# rgb-matrix-backpack-5.net
KiCad netlist of a schematic drawn in EAGLE
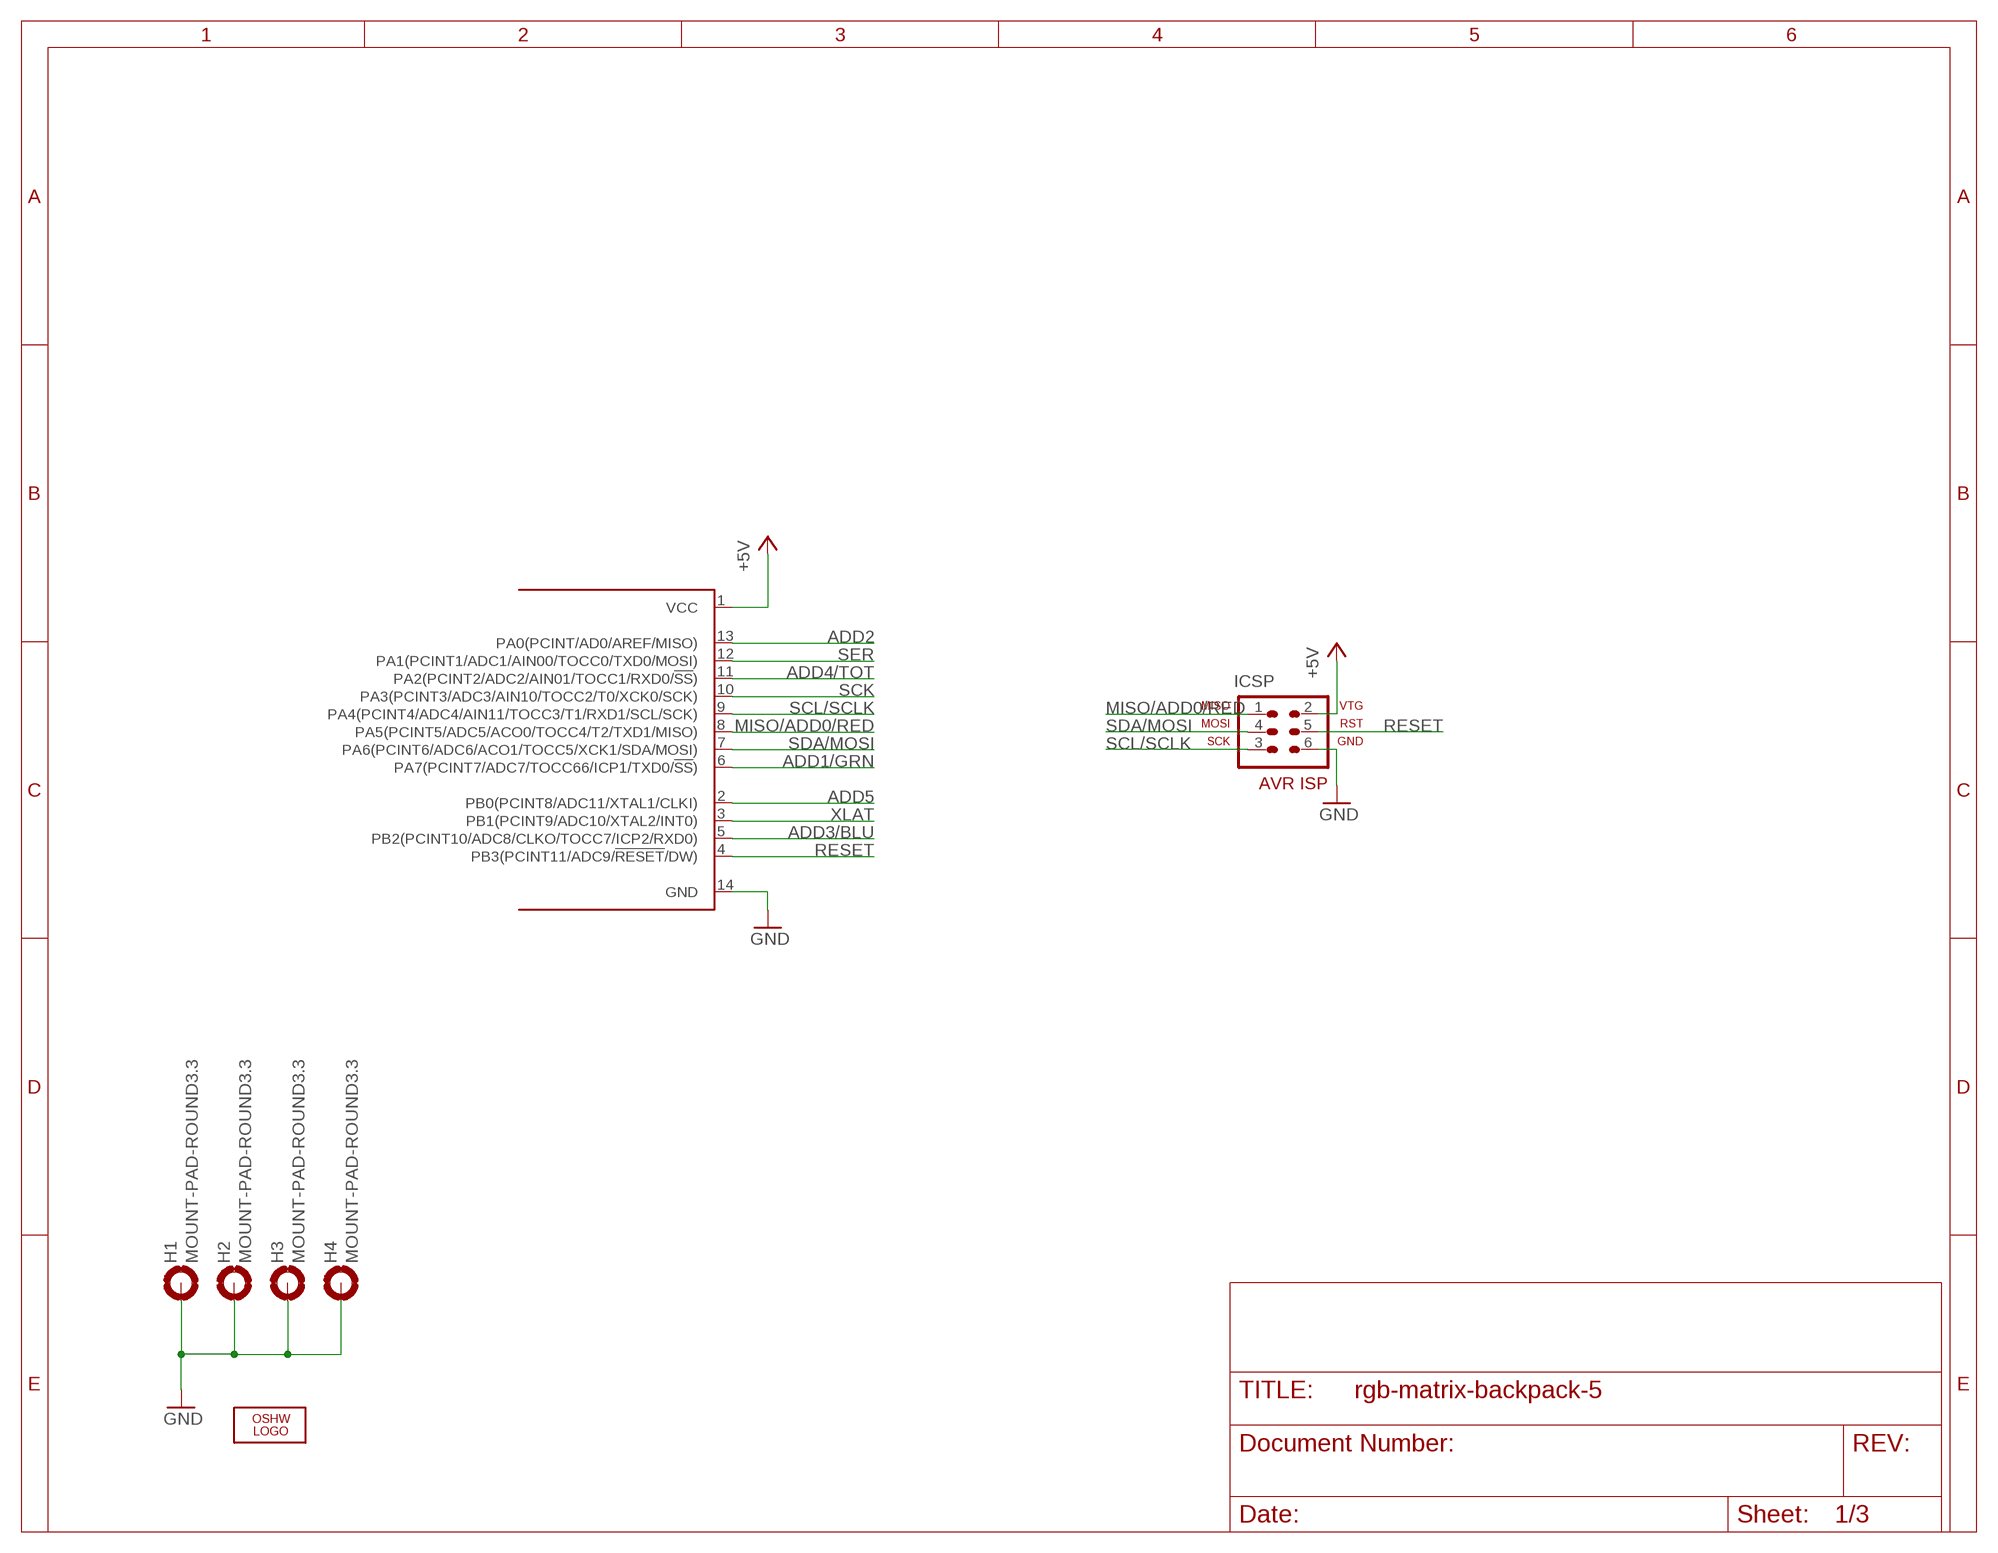
[diagram p0: schematic, sheet 1]
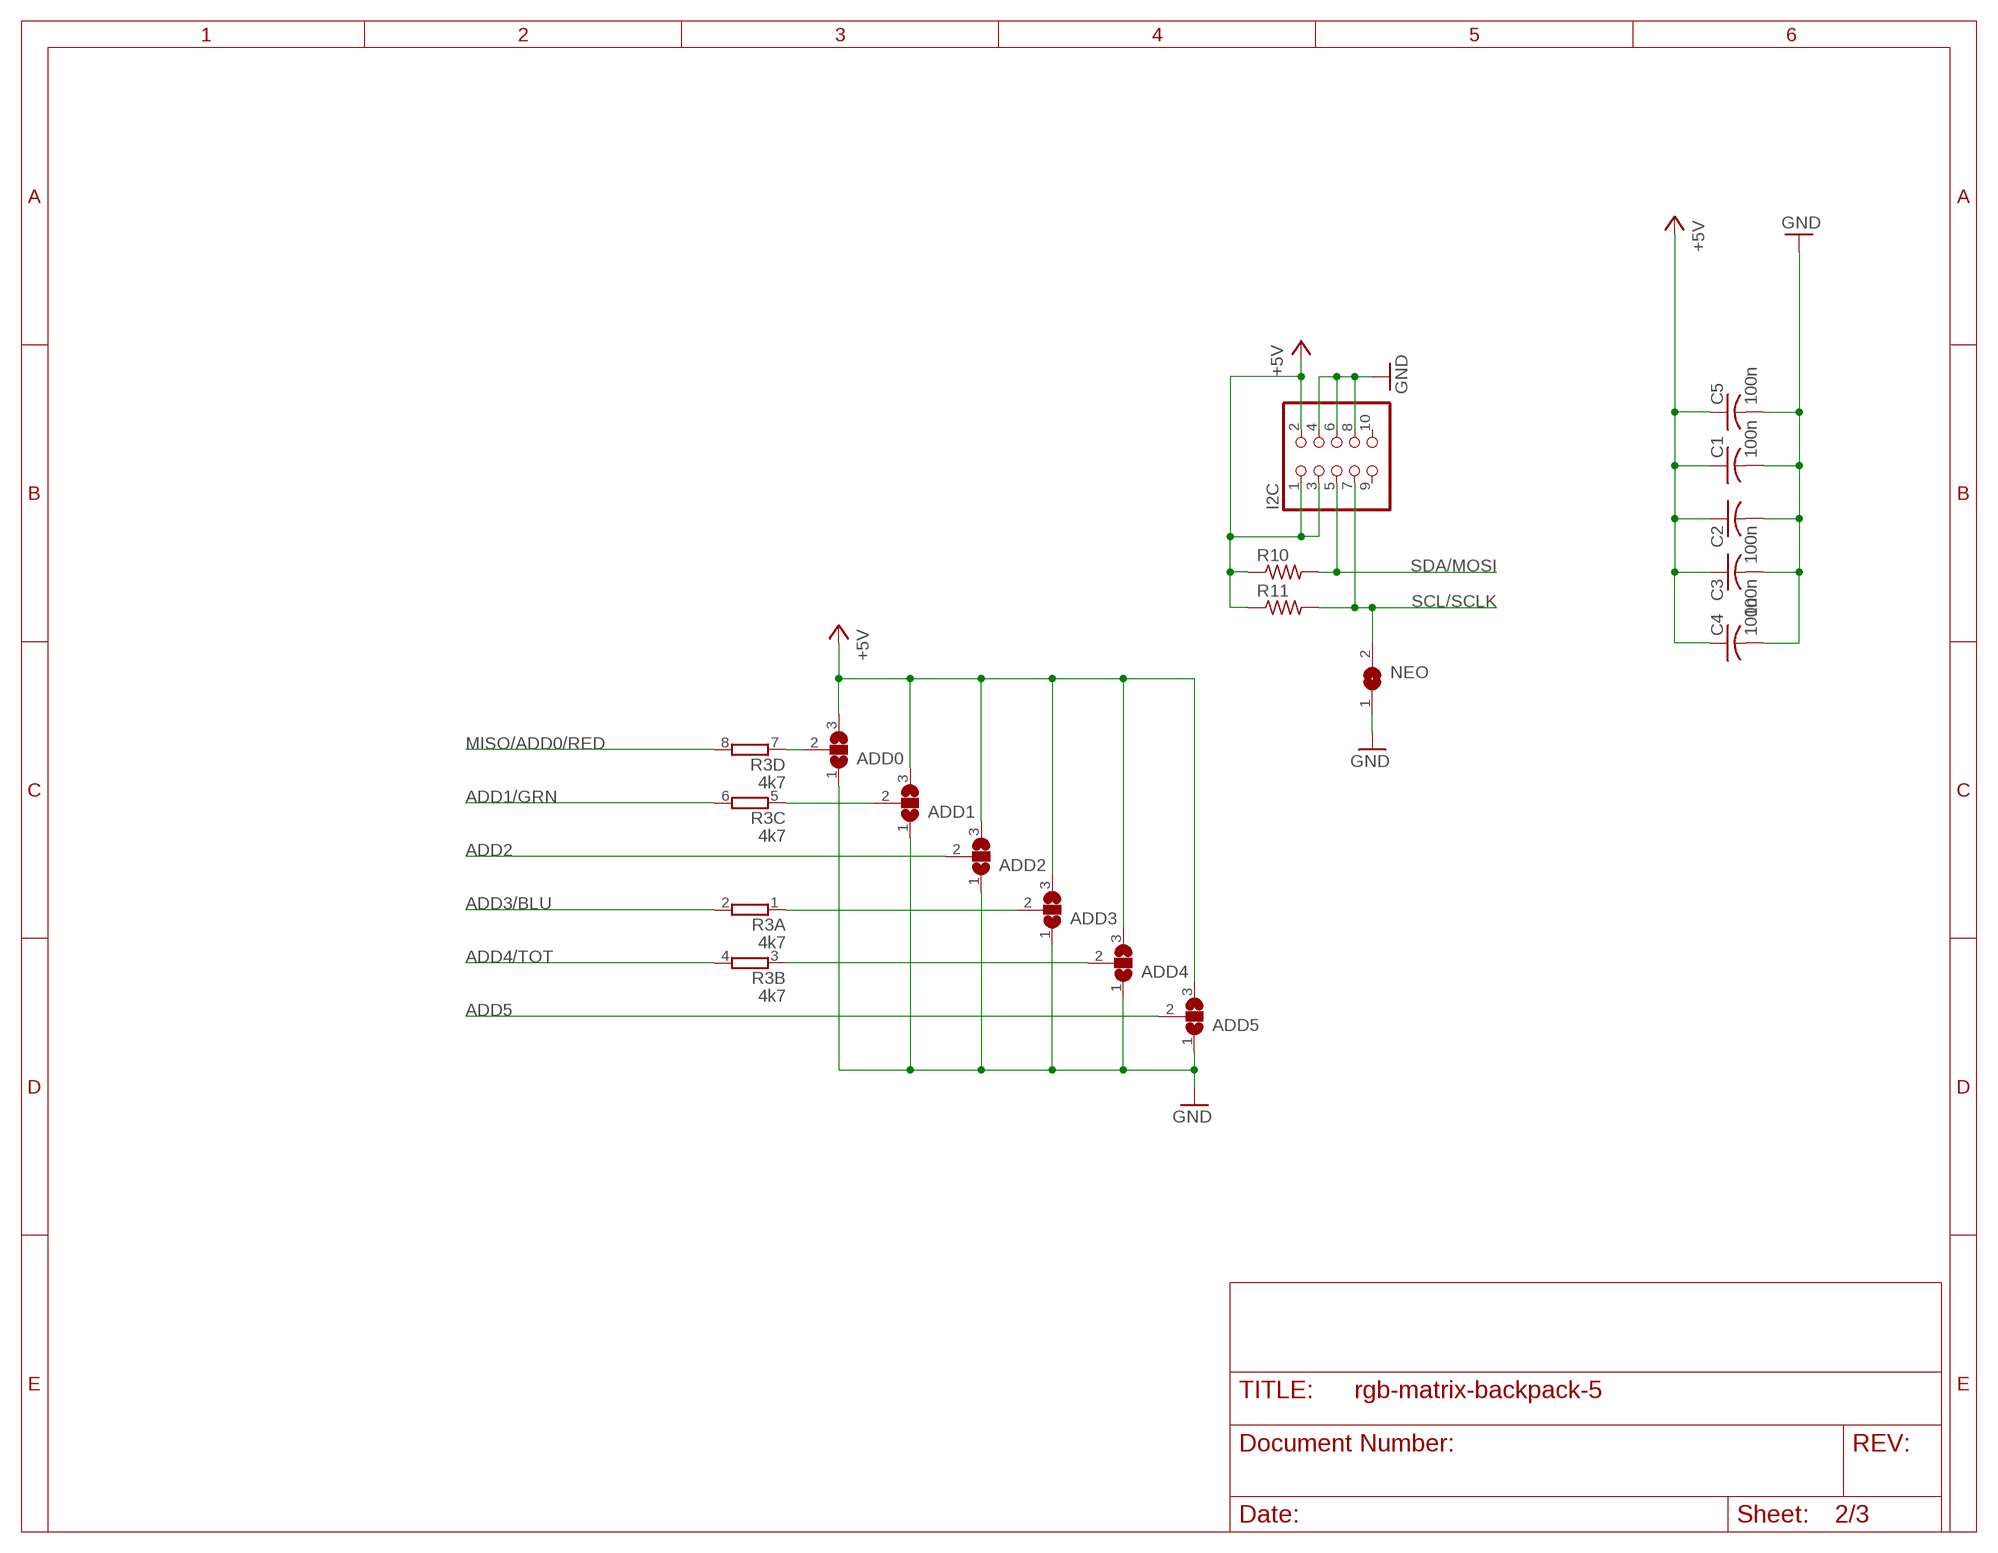
[diagram p1: schematic, sheet 2]
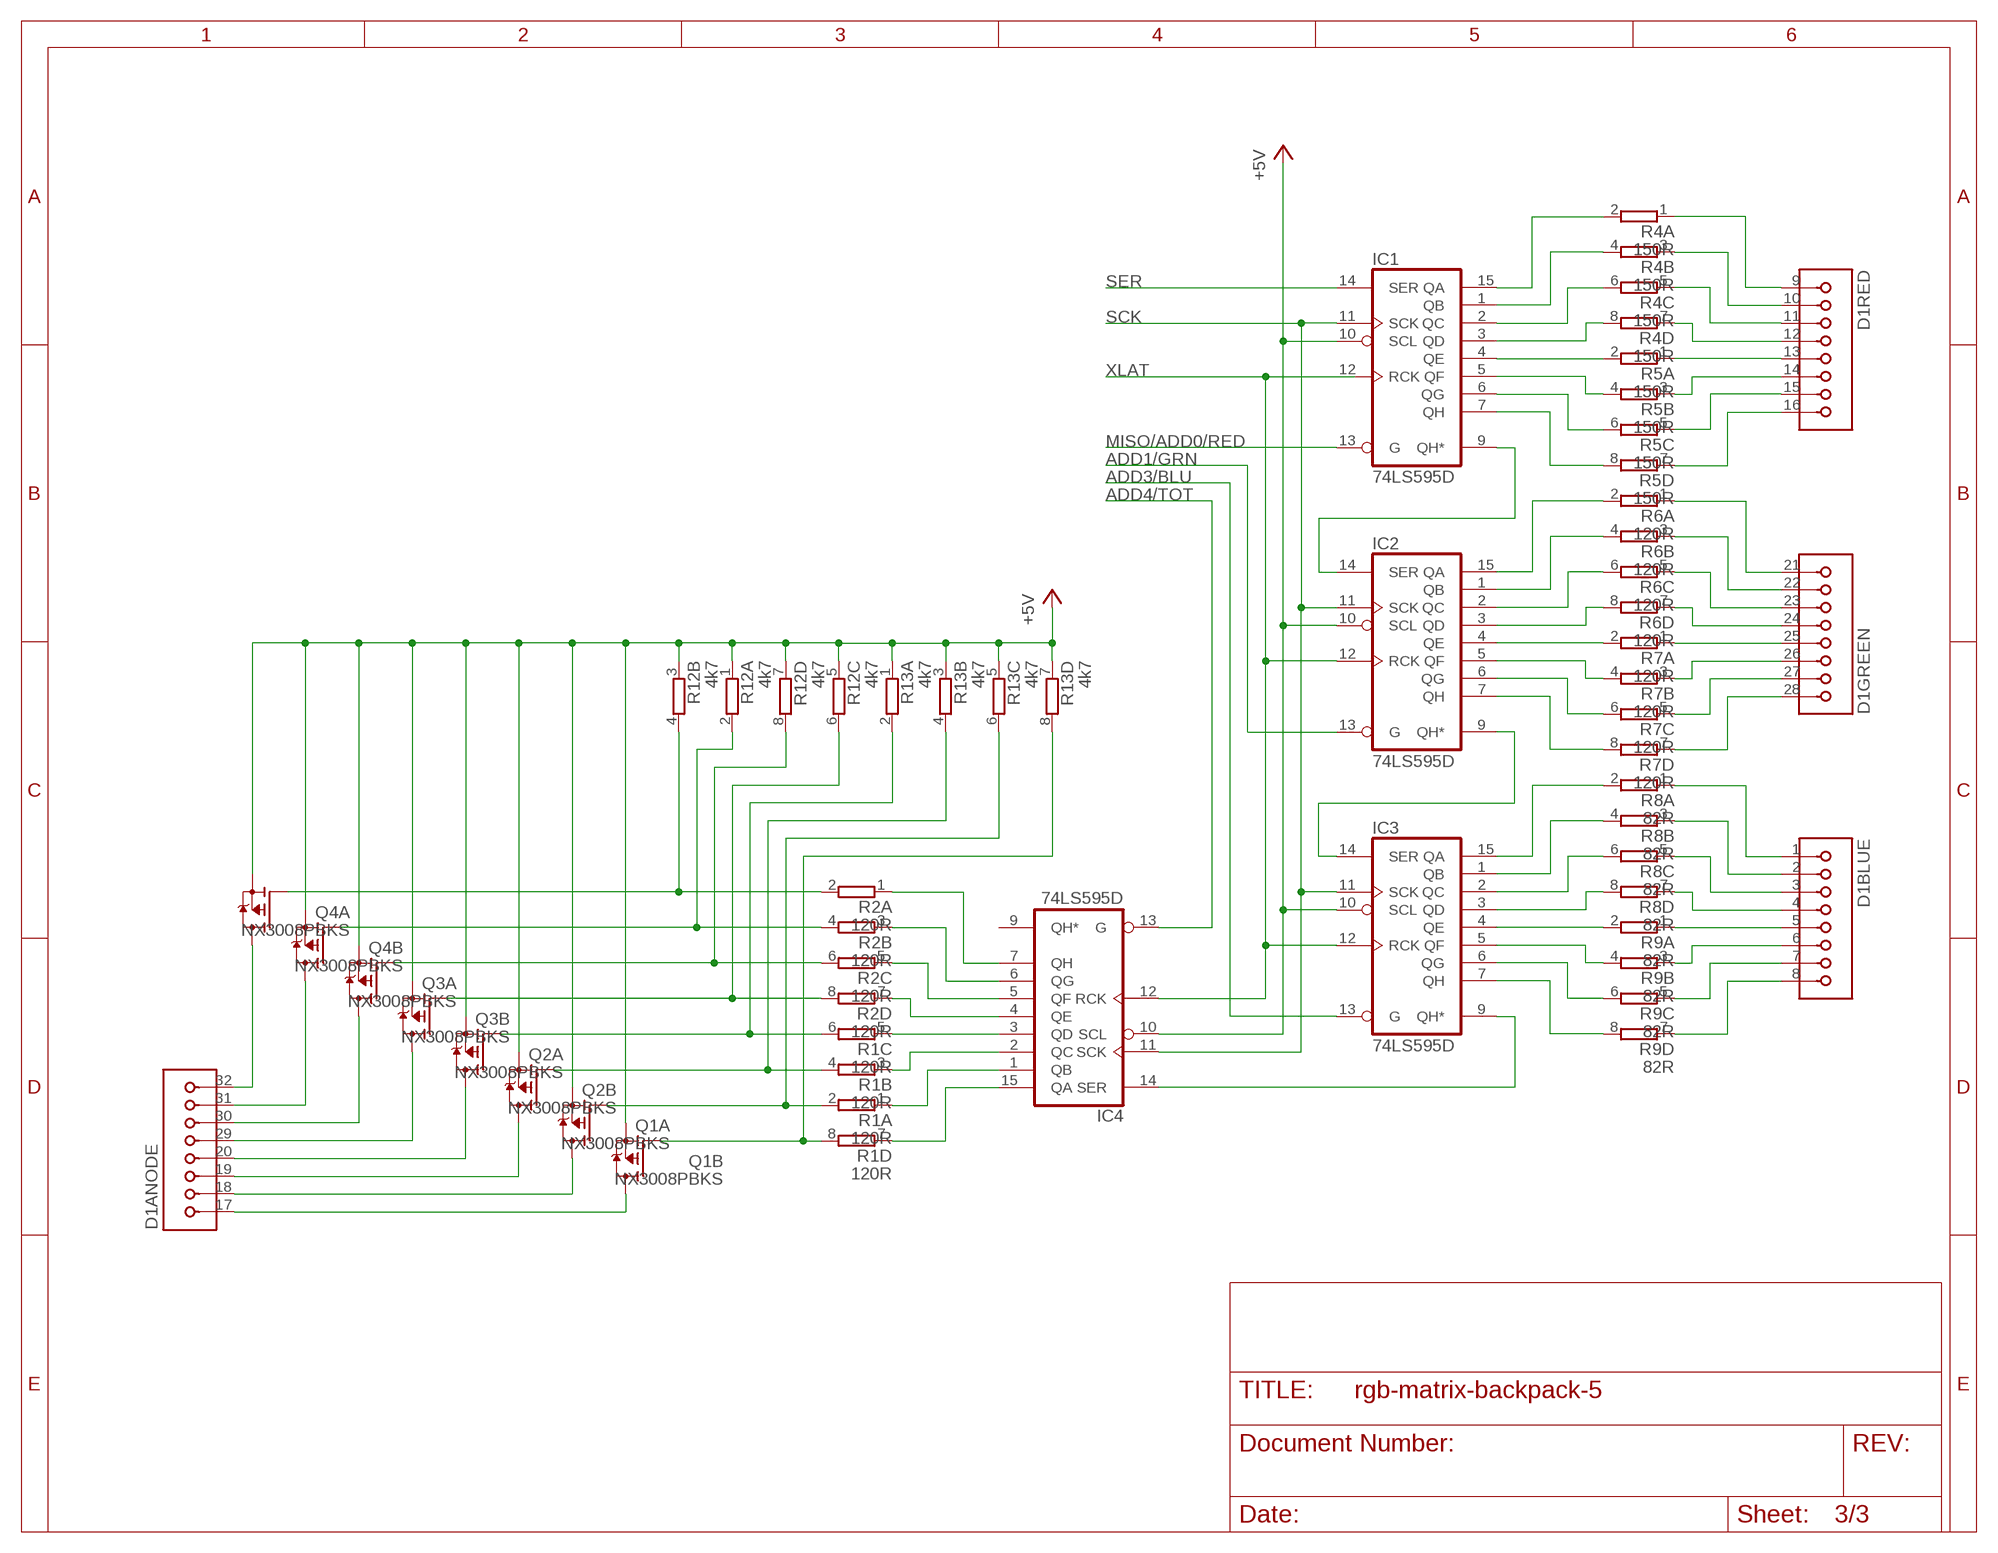
[diagram p2: schematic, sheet 3]

(export (version "E")
  (design (tool "Eeschema 10.0.6"))
  (components
    (comp (ref "D1")
      (value "60MM-8X8-RGB-LED-ARRAY")
      (footprint "eagle-import:60MM-8X8-RGB-MATRIX")
      (fields (field (name "BOM") "EXCLUDE") (field (name "DNP") "T"))
      (libsource (lib "eagle-import") (part "60MM-8X8-RGB-LED-ARRAY"))
    )
    (comp (ref "IC1")
      (value "74LS595D")
      (footprint "eagle-import:SO16")
      (libsource (lib "eagle-import") (part "74595DLS"))
    )
    (comp (ref "IC2")
      (value "74LS595D")
      (footprint "eagle-import:SO16")
      (libsource (lib "eagle-import") (part "74595DLS"))
    )
    (comp (ref "IC3")
      (value "74LS595D")
      (footprint "eagle-import:SO16")
      (libsource (lib "eagle-import") (part "74595DLS"))
    )
    (comp (ref "IC4")
      (value "74LS595D")
      (footprint "eagle-import:SO16")
      (libsource (lib "eagle-import") (part "74595DLS"))
    )
    (comp (ref "Q1")
      (value "NX3008PBKS")
      (footprint "eagle-import:SOT363_INFINEON")
      (fields (field (name "PARTNO") "NX3008PBKS"))
      (libsource (lib "eagle-import") (part "BSD223P"))
    )
    (comp (ref "Q2")
      (value "NX3008PBKS")
      (footprint "eagle-import:SOT363_INFINEON")
      (libsource (lib "eagle-import") (part "BSD223P"))
    )
    (comp (ref "Q3")
      (value "NX3008PBKS")
      (footprint "eagle-import:SOT363_INFINEON")
      (libsource (lib "eagle-import") (part "BSD223P"))
    )
    (comp (ref "Q4")
      (value "NX3008PBKS")
      (footprint "eagle-import:SOT363_INFINEON")
      (libsource (lib "eagle-import") (part "BSD223P"))
    )
    (comp (ref "R1")
      (value "120R")
      (footprint "eagle-import:CTS742C083-RES")
      (fields (field (name "PARTNO") "742C083102JPTR"))
      (libsource (lib "eagle-import") (part "4R-NCTS742C083"))
    )
    (comp (ref "R2")
      (value "120R")
      (footprint "eagle-import:CTS742C083-RES")
      (fields (field (name "PARTNO") "742C083102JPTR"))
      (libsource (lib "eagle-import") (part "4R-NCTS742C083"))
    )
    (comp (ref "R4")
      (value "150R")
      (footprint "eagle-import:CTS742C083-RES")
      (fields (field (name "PARTNO") "742C083102JPTR"))
      (libsource (lib "eagle-import") (part "4R-NCTS742C083"))
    )
    (comp (ref "R5")
      (value "150R")
      (footprint "eagle-import:CTS742C083-RES")
      (fields (field (name "PARTNO") "742C083102JPTR"))
      (libsource (lib "eagle-import") (part "4R-NCTS742C083"))
    )
    (comp (ref "R6")
      (value "120R")
      (footprint "eagle-import:CTS742C083-RES")
      (fields (field (name "PARTNO") "742C083102JPTR"))
      (libsource (lib "eagle-import") (part "4R-NCTS742C083"))
    )
    (comp (ref "R7")
      (value "120R")
      (footprint "eagle-import:CTS742C083-RES")
      (fields (field (name "PARTNO") "742C083102JPTR"))
      (libsource (lib "eagle-import") (part "4R-NCTS742C083"))
    )
    (comp (ref "R8")
      (value "82R")
      (footprint "eagle-import:CTS742C083-RES")
      (fields (field (name "PARTNO") "742C083102JPTR"))
      (libsource (lib "eagle-import") (part "4R-NCTS742C083"))
    )
    (comp (ref "R9")
      (value "82R")
      (footprint "eagle-import:CTS742C083-RES")
      (fields (field (name "PARTNO") "742C083102JPTR"))
      (libsource (lib "eagle-import") (part "4R-NCTS742C083"))
    )
    (comp (ref "R12")
      (value "4k7")
      (footprint "eagle-import:CTS742C083-RES")
      (fields (field (name "PARTNO") "742C083102JPTR"))
      (libsource (lib "eagle-import") (part "4R-NCTS742C083"))
    )
    (comp (ref "R13")
      (value "4k7")
      (footprint "eagle-import:CTS742C083-RES")
      (fields (field (name "PARTNO") "742C083102JPTR"))
      (libsource (lib "eagle-import") (part "4R-NCTS742C083"))
    )
    (comp (ref "H1")
      (value "MOUNT-PAD-ROUND3.3")
      (footprint "eagle-import:3,3-PAD")
      (libsource (lib "eagle-import") (part "MOUNT-PAD-ROUND3.3"))
    )
    (comp (ref "H2")
      (value "MOUNT-PAD-ROUND3.3")
      (footprint "eagle-import:3,3-PAD")
      (libsource (lib "eagle-import") (part "MOUNT-PAD-ROUND3.3"))
    )
    (comp (ref "H3")
      (value "MOUNT-PAD-ROUND3.3")
      (footprint "eagle-import:3,3-PAD")
      (libsource (lib "eagle-import") (part "MOUNT-PAD-ROUND3.3"))
    )
    (comp (ref "H4")
      (value "MOUNT-PAD-ROUND3.3")
      (footprint "eagle-import:3,3-PAD")
      (libsource (lib "eagle-import") (part "MOUNT-PAD-ROUND3.3"))
    )
    (comp (ref "ICSP")
      (value "AVR-ISP-6")
      (footprint "eagle-import:AVR-ISP-6")
      (libsource (lib "eagle-import") (part "AVR-ISP-6"))
    )
    (comp (ref "LOGO1")
      (value "OSHW_LOGO_FILLX0350-NT")
      (footprint "eagle-import:OSHW_FILLX350_NOTEXT")
      (libsource (lib "eagle-import") (part "OSHW_LOGO_FILLX0350-NT"))
    )
    (comp (ref "U1")
      (value "ATTINY841-SU")
      (footprint "eagle-import:SO14")
      (libsource (lib "eagle-import") (part "ATTINY841-SU"))
    )
    (comp (ref "ADD0")
      (value "SJ2W")
      (footprint "eagle-import:SJ_2")
      (libsource (lib "eagle-import") (part "SJ2W"))
    )
    (comp (ref "ADD1")
      (value "SJ2W")
      (footprint "eagle-import:SJ_2")
      (libsource (lib "eagle-import") (part "SJ2W"))
    )
    (comp (ref "ADD2")
      (value "SJ2W")
      (footprint "eagle-import:SJ_2")
      (libsource (lib "eagle-import") (part "SJ2W"))
    )
    (comp (ref "ADD3")
      (value "SJ2W")
      (footprint "eagle-import:SJ_2")
      (libsource (lib "eagle-import") (part "SJ2W"))
    )
    (comp (ref "ADD4")
      (value "SJ2W")
      (footprint "eagle-import:SJ_2")
      (libsource (lib "eagle-import") (part "SJ2W"))
    )
    (comp (ref "ADD5")
      (value "SJ2W")
      (footprint "eagle-import:SJ_2")
      (libsource (lib "eagle-import") (part "SJ2W"))
    )
    (comp (ref "C1")
      (value "100n")
      (footprint "eagle-import:C0603")
      (fields (field (name "PARTNO") "CC0603MRY5V9BB104"))
      (libsource (lib "eagle-import") (part "C-USC0603"))
    )
    (comp (ref "C2")
      (value "100n")
      (footprint "eagle-import:C0603")
      (fields (field (name "PARTNO") "CC0603MRY5V9BB104"))
      (libsource (lib "eagle-import") (part "C-USC0603"))
    )
    (comp (ref "C3")
      (value "100n")
      (footprint "eagle-import:C0603")
      (fields (field (name "PARTNO") "CC0603ZRY5V7BB105"))
      (libsource (lib "eagle-import") (part "C-USC0603"))
    )
    (comp (ref "C4")
      (value "100n")
      (footprint "eagle-import:C0603")
      (fields (field (name "PARTNO") "CC0603MRY5V9BB104"))
      (libsource (lib "eagle-import") (part "C-USC0603"))
    )
    (comp (ref "C5")
      (value "100n")
      (footprint "eagle-import:C0603")
      (fields (field (name "PARTNO") "CC0603MRY5V9BB104"))
      (libsource (lib "eagle-import") (part "C-USC0603"))
    )
    (comp (ref "I2C")
      (value "PINHD-2X5_2.54-90°")
      (footprint "eagle-import:2X05_90")
      (libsource (lib "eagle-import") (part "PINHD-2X5_2.54-90°"))
    )
    (comp (ref "NEO") (value "SJ") (footprint "eagle-import:SJ") (libsource (lib "eagle-import") (part "SJ")))
    (comp (ref "R3")
      (value "4k7")
      (footprint "eagle-import:CTS742C083-RES")
      (fields (field (name "PARTNO") "742C083102JPTR"))
      (libsource (lib "eagle-import") (part "4R-NCTS742C083"))
    )
    (comp (ref "R10")
      (value "R-US_0207/2V")
      (footprint "eagle-import:0207_2V")
      (fields (field (name "PARTNO") "CF14JT4K70"))
      (libsource (lib "eagle-import") (part "R-US_0207/2V"))
    )
    (comp (ref "R11")
      (value "R-US_0207/2V")
      (footprint "eagle-import:0207_2V")
      (fields (field (name "PARTNO") "CF14JT4K70"))
      (libsource (lib "eagle-import") (part "R-US_0207/2V"))
    )
  )
  (nets
    (net (code "1") (name "+5V") (class "Default")
      (node (ref "ADD0") (pin "3") (pinfunction "3_3") (pintype "passive"))
      (node (ref "ADD1") (pin "3") (pinfunction "3_3") (pintype "passive"))
      (node (ref "ADD2") (pin "3") (pinfunction "3_3") (pintype "passive"))
      (node (ref "ADD3") (pin "3") (pinfunction "3_3") (pintype "passive"))
      (node (ref "ADD4") (pin "3") (pinfunction "3_3") (pintype "passive"))
      (node (ref "ADD5") (pin "3") (pinfunction "3_3") (pintype "passive"))
      (node (ref "C1") (pin "1") (pinfunction "1_1") (pintype "passive"))
      (node (ref "C2") (pin "1") (pinfunction "1_1") (pintype "passive"))
      (node (ref "C3") (pin "1") (pinfunction "1_1") (pintype "passive"))
      (node (ref "C4") (pin "1") (pinfunction "1_1") (pintype "passive"))
      (node (ref "C5") (pin "1") (pinfunction "1_1") (pintype "passive"))
      (node (ref "I2C") (pin "1") (pinfunction "1_1") (pintype "passive"))
      (node (ref "I2C") (pin "2") (pinfunction "2_2") (pintype "passive"))
      (node (ref "I2C") (pin "3") (pinfunction "3_3") (pintype "passive"))
      (node (ref "IC1") (pin "10") (pinfunction "SCL_10") (pintype "input"))
      (node (ref "IC2") (pin "10") (pinfunction "SCL_10") (pintype "input"))
      (node (ref "IC3") (pin "10") (pinfunction "SCL_10") (pintype "input"))
      (node (ref "IC4") (pin "10") (pinfunction "SCL_10") (pintype "input"))
      (node (ref "ICSP") (pin "2") (pinfunction "2_2") (pintype "passive"))
      (node (ref "Q1") (pin "1") (pinfunction "S_1") (pintype "passive"))
      (node (ref "Q1") (pin "4") (pinfunction "S_4") (pintype "passive"))
      (node (ref "Q2") (pin "1") (pinfunction "S_1") (pintype "passive"))
      (node (ref "Q2") (pin "4") (pinfunction "S_4") (pintype "passive"))
      (node (ref "Q3") (pin "1") (pinfunction "S_1") (pintype "passive"))
      (node (ref "Q3") (pin "4") (pinfunction "S_4") (pintype "passive"))
      (node (ref "Q4") (pin "1") (pinfunction "S_1") (pintype "passive"))
      (node (ref "Q4") (pin "4") (pinfunction "S_4") (pintype "passive"))
      (node (ref "R10") (pin "1") (pinfunction "1_1") (pintype "passive"))
      (node (ref "R11") (pin "1") (pinfunction "1_1") (pintype "passive"))
      (node (ref "R12") (pin "1") (pinfunction "1_1") (pintype "passive"))
      (node (ref "R12") (pin "3") (pinfunction "1_3") (pintype "passive"))
      (node (ref "R12") (pin "5") (pinfunction "1_5") (pintype "passive"))
      (node (ref "R12") (pin "7") (pinfunction "1_7") (pintype "passive"))
      (node (ref "R13") (pin "1") (pinfunction "1_1") (pintype "passive"))
      (node (ref "R13") (pin "3") (pinfunction "1_3") (pintype "passive"))
      (node (ref "R13") (pin "5") (pinfunction "1_5") (pintype "passive"))
      (node (ref "R13") (pin "7") (pinfunction "1_7") (pintype "passive"))
      (node (ref "U1") (pin "1") (pinfunction "VCC_1") (pintype "bidirectional"))
    )
    (net (code "2") (name "ADD1{slash}GRN") (class "Default")
      (node (ref "IC2") (pin "13") (pinfunction "G_13") (pintype "input"))
      (node (ref "R3") (pin "6") (pinfunction "2_6") (pintype "passive"))
      (node (ref "U1") (pin "6") (pinfunction "PA7(PCINT7/ADC7/TOCC66/ICP1/TXD0/~{SS})_6") (pintype "bidirectional"))
    )
    (net (code "3") (name "ADD2") (class "Default")
      (node (ref "ADD2") (pin "2") (pinfunction "2_2") (pintype "passive"))
      (node (ref "U1") (pin "13") (pinfunction "PA0(PCINT/AD0/AREF/MISO)_13") (pintype "bidirectional"))
    )
    (net (code "4") (name "ADD3{slash}BLU") (class "Default")
      (node (ref "IC3") (pin "13") (pinfunction "G_13") (pintype "input"))
      (node (ref "R3") (pin "2") (pinfunction "2_2") (pintype "passive"))
      (node (ref "U1") (pin "5") (pinfunction "PB2(PCINT10/ADC8/CLKO/TOCC7/ICP2/RXD0)_5") (pintype "bidirectional"))
    )
    (net (code "5") (name "ADD4{slash}TOT") (class "Default")
      (node (ref "IC4") (pin "13") (pinfunction "G_13") (pintype "input"))
      (node (ref "R3") (pin "4") (pinfunction "2_4") (pintype "passive"))
      (node (ref "U1") (pin "11") (pinfunction "PA2(PCINT2/ADC2/AIN01/TOCC1/RXD0/~{SS})_11") (pintype "bidirectional"))
    )
    (net (code "6") (name "ADD5") (class "Default")
      (node (ref "ADD5") (pin "2") (pinfunction "2_2") (pintype "passive"))
      (node (ref "U1") (pin "2") (pinfunction "PB0(PCINT8/ADC11/XTAL1/CLKI)_2") (pintype "bidirectional"))
    )
    (net (code "7") (name "GND") (class "Default")
      (node (ref "ADD0") (pin "1") (pinfunction "1_1") (pintype "passive"))
      (node (ref "ADD1") (pin "1") (pinfunction "1_1") (pintype "passive"))
      (node (ref "ADD2") (pin "1") (pinfunction "1_1") (pintype "passive"))
      (node (ref "ADD3") (pin "1") (pinfunction "1_1") (pintype "passive"))
      (node (ref "ADD4") (pin "1") (pinfunction "1_1") (pintype "passive"))
      (node (ref "ADD5") (pin "1") (pinfunction "1_1") (pintype "passive"))
      (node (ref "C1") (pin "2") (pinfunction "2_2") (pintype "passive"))
      (node (ref "C2") (pin "2") (pinfunction "2_2") (pintype "passive"))
      (node (ref "C3") (pin "2") (pinfunction "2_2") (pintype "passive"))
      (node (ref "C4") (pin "2") (pinfunction "2_2") (pintype "passive"))
      (node (ref "C5") (pin "2") (pinfunction "2_2") (pintype "passive"))
      (node (ref "H1") (pin "B3,3") (pinfunction "MOUNT_B3,3") (pintype "passive"))
      (node (ref "H2") (pin "B3,3") (pinfunction "MOUNT_B3,3") (pintype "passive"))
      (node (ref "H3") (pin "B3,3") (pinfunction "MOUNT_B3,3") (pintype "passive"))
      (node (ref "H4") (pin "B3,3") (pinfunction "MOUNT_B3,3") (pintype "passive"))
      (node (ref "I2C") (pin "4") (pinfunction "4_4") (pintype "passive"))
      (node (ref "I2C") (pin "6") (pinfunction "6_6") (pintype "passive"))
      (node (ref "I2C") (pin "8") (pinfunction "8_8") (pintype "passive"))
      (node (ref "ICSP") (pin "6") (pinfunction "6_6") (pintype "passive"))
      (node (ref "NEO") (pin "1") (pinfunction "1_1") (pintype "passive"))
      (node (ref "U1") (pin "14") (pinfunction "GND_14") (pintype "bidirectional"))
    )
    (net (code "8") (name "MISO{slash}ADD0{slash}RED") (class "Default")
      (node (ref "IC1") (pin "13") (pinfunction "G_13") (pintype "input"))
      (node (ref "ICSP") (pin "1") (pinfunction "1_1") (pintype "passive"))
      (node (ref "R3") (pin "8") (pinfunction "2_8") (pintype "passive"))
      (node (ref "U1") (pin "8") (pinfunction "PA5(PCINT5/ADC5/ACO0/TOCC4/T2/TXD1/MISO)_8") (pintype "bidirectional"))
    )
    (net (code "9") (name "Net-(ADD3-Pad2)") (class "Default")
      (node (ref "ADD3") (pin "2") (pinfunction "2_2") (pintype "passive"))
      (node (ref "R3") (pin "1") (pinfunction "1_1") (pintype "passive"))
    )
    (net (code "10") (name "Net-(D1-Pad1)") (class "Default")
      (node (ref "D1") (pin "1") (pinfunction "1_1") (pintype "bidirectional"))
      (node (ref "R8") (pin "1") (pinfunction "1_1") (pintype "passive"))
    )
    (net (code "11") (name "Net-(D1-Pad5)") (class "Default")
      (node (ref "D1") (pin "5") (pinfunction "5_5") (pintype "bidirectional"))
      (node (ref "R9") (pin "1") (pinfunction "1_1") (pintype "passive"))
    )
    (net (code "12") (name "Net-(D1A-1)") (class "Default")
      (node (ref "D1") (pin "17") (pinfunction "1_17") (pintype "bidirectional"))
      (node (ref "Q1") (pin "3") (pinfunction "D_3") (pintype "passive"))
    )
    (net (code "13") (name "Net-(D1A-2)") (class "Default")
      (node (ref "D1") (pin "18") (pinfunction "2_18") (pintype "bidirectional"))
      (node (ref "Q1") (pin "6") (pinfunction "D_6") (pintype "passive"))
    )
    (net (code "14") (name "Net-(D1A-3)") (class "Default")
      (node (ref "D1") (pin "19") (pinfunction "3_19") (pintype "bidirectional"))
      (node (ref "Q2") (pin "3") (pinfunction "D_3") (pintype "passive"))
    )
    (net (code "15") (name "Net-(D1A-4)") (class "Default")
      (node (ref "D1") (pin "20") (pinfunction "4_20") (pintype "bidirectional"))
      (node (ref "Q2") (pin "6") (pinfunction "D_6") (pintype "passive"))
    )
    (net (code "16") (name "Net-(D1A-5)") (class "Default")
      (node (ref "D1") (pin "29") (pinfunction "5_29") (pintype "bidirectional"))
      (node (ref "Q3") (pin "3") (pinfunction "D_3") (pintype "passive"))
    )
    (net (code "17") (name "Net-(D1A-6)") (class "Default")
      (node (ref "D1") (pin "30") (pinfunction "6_30") (pintype "bidirectional"))
      (node (ref "Q3") (pin "6") (pinfunction "D_6") (pintype "passive"))
    )
    (net (code "18") (name "Net-(D1A-7)") (class "Default")
      (node (ref "D1") (pin "31") (pinfunction "7_31") (pintype "bidirectional"))
      (node (ref "Q4") (pin "3") (pinfunction "D_3") (pintype "passive"))
    )
    (net (code "19") (name "Net-(D1A-8)") (class "Default")
      (node (ref "D1") (pin "32") (pinfunction "8_32") (pintype "bidirectional"))
      (node (ref "Q4") (pin "6") (pinfunction "D_6") (pintype "passive"))
    )
    (net (code "20") (name "Net-(D1C-1)") (class "Default")
      (node (ref "D1") (pin "28") (pinfunction "1_28") (pintype "bidirectional"))
      (node (ref "R7") (pin "7") (pinfunction "1_7") (pintype "passive"))
    )
    (net (code "21") (name "Net-(D1C-2)") (class "Default")
      (node (ref "D1") (pin "27") (pinfunction "2_27") (pintype "bidirectional"))
      (node (ref "R7") (pin "5") (pinfunction "1_5") (pintype "passive"))
    )
    (net (code "22") (name "Net-(D1C-3)") (class "Default")
      (node (ref "D1") (pin "26") (pinfunction "3_26") (pintype "bidirectional"))
      (node (ref "R7") (pin "3") (pinfunction "1_3") (pintype "passive"))
    )
    (net (code "23") (name "Net-(D1C-4)") (class "Default")
      (node (ref "D1") (pin "25") (pinfunction "4_25") (pintype "bidirectional"))
      (node (ref "R7") (pin "1") (pinfunction "1_1") (pintype "passive"))
    )
    (net (code "24") (name "Net-(D1C-5)") (class "Default")
      (node (ref "D1") (pin "24") (pinfunction "5_24") (pintype "bidirectional"))
      (node (ref "R6") (pin "7") (pinfunction "1_7") (pintype "passive"))
    )
    (net (code "25") (name "Net-(D1C-6)") (class "Default")
      (node (ref "D1") (pin "23") (pinfunction "6_23") (pintype "bidirectional"))
      (node (ref "R6") (pin "5") (pinfunction "1_5") (pintype "passive"))
    )
    (net (code "26") (name "Net-(D1C-7)") (class "Default")
      (node (ref "D1") (pin "22") (pinfunction "7_22") (pintype "bidirectional"))
      (node (ref "R6") (pin "3") (pinfunction "1_3") (pintype "passive"))
    )
    (net (code "27") (name "Net-(D1C-8)") (class "Default")
      (node (ref "D1") (pin "21") (pinfunction "8_21") (pintype "bidirectional"))
      (node (ref "R6") (pin "1") (pinfunction "1_1") (pintype "passive"))
    )
    (net (code "28") (name "Net-(D1D-1)") (class "Default")
      (node (ref "D1") (pin "9") (pinfunction "1_9") (pintype "bidirectional"))
      (node (ref "R4") (pin "1") (pinfunction "1_1") (pintype "passive"))
    )
    (net (code "29") (name "Net-(D1D-2)") (class "Default")
      (node (ref "D1") (pin "10") (pinfunction "2_10") (pintype "bidirectional"))
      (node (ref "R4") (pin "3") (pinfunction "1_3") (pintype "passive"))
    )
    (net (code "30") (name "Net-(D1D-3)") (class "Default")
      (node (ref "D1") (pin "11") (pinfunction "3_11") (pintype "bidirectional"))
      (node (ref "R4") (pin "5") (pinfunction "1_5") (pintype "passive"))
    )
    (net (code "31") (name "Net-(D1D-4)") (class "Default")
      (node (ref "D1") (pin "12") (pinfunction "4_12") (pintype "bidirectional"))
      (node (ref "R4") (pin "7") (pinfunction "1_7") (pintype "passive"))
    )
    (net (code "32") (name "Net-(D1D-5)") (class "Default")
      (node (ref "D1") (pin "13") (pinfunction "5_13") (pintype "bidirectional"))
      (node (ref "R5") (pin "1") (pinfunction "1_1") (pintype "passive"))
    )
    (net (code "33") (name "Net-(D1D-6)") (class "Default")
      (node (ref "D1") (pin "14") (pinfunction "6_14") (pintype "bidirectional"))
      (node (ref "R5") (pin "3") (pinfunction "1_3") (pintype "passive"))
    )
    (net (code "34") (name "Net-(D1D-7)") (class "Default")
      (node (ref "D1") (pin "15") (pinfunction "7_15") (pintype "bidirectional"))
      (node (ref "R5") (pin "5") (pinfunction "1_5") (pintype "passive"))
    )
    (net (code "35") (name "Net-(D1D-8)") (class "Default")
      (node (ref "D1") (pin "16") (pinfunction "8_16") (pintype "bidirectional"))
      (node (ref "R5") (pin "7") (pinfunction "1_7") (pintype "passive"))
    )
    (net (code "36") (name "Net-(IC1A-QA)") (class "Default")
      (node (ref "IC1") (pin "15") (pinfunction "QA_15") (pintype "tri_state"))
      (node (ref "R4") (pin "2") (pinfunction "2_2") (pintype "passive"))
    )
    (net (code "37") (name "Net-(IC1A-QB)") (class "Default")
      (node (ref "IC1") (pin "1") (pinfunction "QB_1") (pintype "tri_state"))
      (node (ref "R4") (pin "4") (pinfunction "2_4") (pintype "passive"))
    )
    (net (code "38") (name "Net-(IC1A-QC)") (class "Default")
      (node (ref "IC1") (pin "2") (pinfunction "QC_2") (pintype "tri_state"))
      (node (ref "R4") (pin "6") (pinfunction "2_6") (pintype "passive"))
    )
    (net (code "39") (name "Net-(IC1A-QD)") (class "Default")
      (node (ref "IC1") (pin "3") (pinfunction "QD_3") (pintype "tri_state"))
      (node (ref "R4") (pin "8") (pinfunction "2_8") (pintype "passive"))
    )
    (net (code "40") (name "Net-(IC1A-QE)") (class "Default")
      (node (ref "IC1") (pin "4") (pinfunction "QE_4") (pintype "tri_state"))
      (node (ref "R5") (pin "2") (pinfunction "2_2") (pintype "passive"))
    )
    (net (code "41") (name "Net-(IC1A-QF)") (class "Default")
      (node (ref "IC1") (pin "5") (pinfunction "QF_5") (pintype "tri_state"))
      (node (ref "R5") (pin "4") (pinfunction "2_4") (pintype "passive"))
    )
    (net (code "42") (name "Net-(IC1A-QG)") (class "Default")
      (node (ref "IC1") (pin "6") (pinfunction "QG_6") (pintype "tri_state"))
      (node (ref "R5") (pin "6") (pinfunction "2_6") (pintype "passive"))
    )
    (net (code "43") (name "Net-(IC1A-QH)") (class "Default")
      (node (ref "IC1") (pin "7") (pinfunction "QH_7") (pintype "tri_state"))
      (node (ref "R5") (pin "8") (pinfunction "2_8") (pintype "passive"))
    )
    (net (code "44") (name "Net-(IC1A-QH*)") (class "Default")
      (node (ref "IC1") (pin "9") (pinfunction "QH*_9") (pintype "tri_state"))
      (node (ref "IC2") (pin "14") (pinfunction "SER_14") (pintype "input"))
    )
    (net (code "45") (name "Net-(IC2A-QA)") (class "Default")
      (node (ref "IC2") (pin "15") (pinfunction "QA_15") (pintype "tri_state"))
      (node (ref "R6") (pin "2") (pinfunction "2_2") (pintype "passive"))
    )
    (net (code "46") (name "Net-(IC2A-QB)") (class "Default")
      (node (ref "IC2") (pin "1") (pinfunction "QB_1") (pintype "tri_state"))
      (node (ref "R6") (pin "4") (pinfunction "2_4") (pintype "passive"))
    )
    (net (code "47") (name "Net-(IC2A-QC)") (class "Default")
      (node (ref "IC2") (pin "2") (pinfunction "QC_2") (pintype "tri_state"))
      (node (ref "R6") (pin "6") (pinfunction "2_6") (pintype "passive"))
    )
    (net (code "48") (name "Net-(IC2A-QD)") (class "Default")
      (node (ref "IC2") (pin "3") (pinfunction "QD_3") (pintype "tri_state"))
      (node (ref "R6") (pin "8") (pinfunction "2_8") (pintype "passive"))
    )
    (net (code "49") (name "Net-(IC2A-QE)") (class "Default")
      (node (ref "IC2") (pin "4") (pinfunction "QE_4") (pintype "tri_state"))
      (node (ref "R7") (pin "2") (pinfunction "2_2") (pintype "passive"))
    )
    (net (code "50") (name "Net-(IC2A-QF)") (class "Default")
      (node (ref "IC2") (pin "5") (pinfunction "QF_5") (pintype "tri_state"))
      (node (ref "R7") (pin "4") (pinfunction "2_4") (pintype "passive"))
    )
    (net (code "51") (name "Net-(IC2A-QG)") (class "Default")
      (node (ref "IC2") (pin "6") (pinfunction "QG_6") (pintype "tri_state"))
      (node (ref "R7") (pin "6") (pinfunction "2_6") (pintype "passive"))
    )
    (net (code "52") (name "Net-(IC2A-QH)") (class "Default")
      (node (ref "IC2") (pin "7") (pinfunction "QH_7") (pintype "tri_state"))
      (node (ref "R7") (pin "8") (pinfunction "2_8") (pintype "passive"))
    )
    (net (code "53") (name "Net-(IC2A-QH*)") (class "Default")
      (node (ref "IC2") (pin "9") (pinfunction "QH*_9") (pintype "tri_state"))
      (node (ref "IC3") (pin "14") (pinfunction "SER_14") (pintype "input"))
    )
    (net (code "54") (name "Net-(IC3A-QA)") (class "Default")
      (node (ref "IC3") (pin "15") (pinfunction "QA_15") (pintype "tri_state"))
      (node (ref "R8") (pin "2") (pinfunction "2_2") (pintype "passive"))
    )
    (net (code "55") (name "Net-(IC3A-QB)") (class "Default")
      (node (ref "IC3") (pin "1") (pinfunction "QB_1") (pintype "tri_state"))
      (node (ref "R8") (pin "4") (pinfunction "2_4") (pintype "passive"))
    )
    (net (code "56") (name "Net-(IC3A-QC)") (class "Default")
      (node (ref "IC3") (pin "2") (pinfunction "QC_2") (pintype "tri_state"))
      (node (ref "R8") (pin "6") (pinfunction "2_6") (pintype "passive"))
    )
    (net (code "57") (name "Net-(IC3A-QD)") (class "Default")
      (node (ref "IC3") (pin "3") (pinfunction "QD_3") (pintype "tri_state"))
      (node (ref "R8") (pin "8") (pinfunction "2_8") (pintype "passive"))
    )
    (net (code "58") (name "Net-(IC3A-QE)") (class "Default")
      (node (ref "IC3") (pin "4") (pinfunction "QE_4") (pintype "tri_state"))
      (node (ref "R9") (pin "2") (pinfunction "2_2") (pintype "passive"))
    )
    (net (code "59") (name "Net-(IC3A-QF)") (class "Default")
      (node (ref "IC3") (pin "5") (pinfunction "QF_5") (pintype "tri_state"))
      (node (ref "R9") (pin "4") (pinfunction "2_4") (pintype "passive"))
    )
    (net (code "60") (name "Net-(IC3A-QG)") (class "Default")
      (node (ref "IC3") (pin "6") (pinfunction "QG_6") (pintype "tri_state"))
      (node (ref "R9") (pin "6") (pinfunction "2_6") (pintype "passive"))
    )
    (net (code "61") (name "Net-(IC3A-QH)") (class "Default")
      (node (ref "IC3") (pin "7") (pinfunction "QH_7") (pintype "tri_state"))
      (node (ref "R9") (pin "8") (pinfunction "2_8") (pintype "passive"))
    )
    (net (code "62") (name "Net-(IC3A-QH*)") (class "Default")
      (node (ref "IC3") (pin "9") (pinfunction "QH*_9") (pintype "tri_state"))
      (node (ref "IC4") (pin "14") (pinfunction "SER_14") (pintype "input"))
    )
    (net (code "63") (name "Net-(IC4A-QA)") (class "Default")
      (node (ref "IC4") (pin "15") (pinfunction "QA_15") (pintype "tri_state"))
      (node (ref "R1") (pin "7") (pinfunction "1_7") (pintype "passive"))
    )
    (net (code "64") (name "Net-(IC4A-QB)") (class "Default")
      (node (ref "IC4") (pin "1") (pinfunction "QB_1") (pintype "tri_state"))
      (node (ref "R1") (pin "1") (pinfunction "1_1") (pintype "passive"))
    )
    (net (code "65") (name "Net-(IC4A-QC)") (class "Default")
      (node (ref "IC4") (pin "2") (pinfunction "QC_2") (pintype "tri_state"))
      (node (ref "R1") (pin "3") (pinfunction "1_3") (pintype "passive"))
    )
    (net (code "66") (name "Net-(IC4A-QD)") (class "Default")
      (node (ref "IC4") (pin "3") (pinfunction "QD_3") (pintype "tri_state"))
      (node (ref "R1") (pin "5") (pinfunction "1_5") (pintype "passive"))
    )
    (net (code "67") (name "Net-(IC4A-QE)") (class "Default")
      (node (ref "IC4") (pin "4") (pinfunction "QE_4") (pintype "tri_state"))
      (node (ref "R2") (pin "7") (pinfunction "1_7") (pintype "passive"))
    )
    (net (code "68") (name "Net-(IC4A-QF)") (class "Default")
      (node (ref "IC4") (pin "5") (pinfunction "QF_5") (pintype "tri_state"))
      (node (ref "R2") (pin "5") (pinfunction "1_5") (pintype "passive"))
    )
    (net (code "69") (name "Net-(IC4A-QG)") (class "Default")
      (node (ref "IC4") (pin "6") (pinfunction "QG_6") (pintype "tri_state"))
      (node (ref "R2") (pin "3") (pinfunction "1_3") (pintype "passive"))
    )
    (net (code "70") (name "Net-(IC4A-QH)") (class "Default")
      (node (ref "IC4") (pin "7") (pinfunction "QH_7") (pintype "tri_state"))
      (node (ref "R2") (pin "1") (pinfunction "1_1") (pintype "passive"))
    )
    (net (code "71") (name "Net-(Q1A-G)") (class "Default")
      (node (ref "Q1") (pin "2") (pinfunction "G_2") (pintype "passive"))
      (node (ref "R1") (pin "2") (pinfunction "2_2") (pintype "passive"))
      (node (ref "R13") (pin "6") (pinfunction "2_6") (pintype "passive"))
    )
    (net (code "72") (name "Net-(Q1B-G)") (class "Default")
      (node (ref "Q1") (pin "5") (pinfunction "G_5") (pintype "passive"))
      (node (ref "R1") (pin "8") (pinfunction "2_8") (pintype "passive"))
      (node (ref "R13") (pin "8") (pinfunction "2_8") (pintype "passive"))
    )
    (net (code "73") (name "Net-(Q2A-G)") (class "Default")
      (node (ref "Q2") (pin "2") (pinfunction "G_2") (pintype "passive"))
      (node (ref "R1") (pin "6") (pinfunction "2_6") (pintype "passive"))
      (node (ref "R13") (pin "2") (pinfunction "2_2") (pintype "passive"))
    )
    (net (code "74") (name "Net-(Q2B-G)") (class "Default")
      (node (ref "Q2") (pin "5") (pinfunction "G_5") (pintype "passive"))
      (node (ref "R1") (pin "4") (pinfunction "2_4") (pintype "passive"))
      (node (ref "R13") (pin "4") (pinfunction "2_4") (pintype "passive"))
    )
    (net (code "75") (name "Net-(Q3A-G)") (class "Default")
      (node (ref "Q3") (pin "2") (pinfunction "G_2") (pintype "passive"))
      (node (ref "R12") (pin "8") (pinfunction "2_8") (pintype "passive"))
      (node (ref "R2") (pin "6") (pinfunction "2_6") (pintype "passive"))
    )
    (net (code "76") (name "Net-(Q3B-G)") (class "Default")
      (node (ref "Q3") (pin "5") (pinfunction "G_5") (pintype "passive"))
      (node (ref "R12") (pin "6") (pinfunction "2_6") (pintype "passive"))
      (node (ref "R2") (pin "8") (pinfunction "2_8") (pintype "passive"))
    )
    (net (code "77") (name "Net-(Q4A-G)") (class "Default")
      (node (ref "Q4") (pin "2") (pinfunction "G_2") (pintype "passive"))
      (node (ref "R12") (pin "4") (pinfunction "2_4") (pintype "passive"))
      (node (ref "R2") (pin "2") (pinfunction "2_2") (pintype "passive"))
    )
    (net (code "78") (name "Net-(Q4B-G)") (class "Default")
      (node (ref "Q4") (pin "5") (pinfunction "G_5") (pintype "passive"))
      (node (ref "R12") (pin "2") (pinfunction "2_2") (pintype "passive"))
      (node (ref "R2") (pin "4") (pinfunction "2_4") (pintype "passive"))
    )
    (net (code "79") (name "Net-(R3B-1)") (class "Default")
      (node (ref "ADD4") (pin "2") (pinfunction "2_2") (pintype "passive"))
      (node (ref "R3") (pin "3") (pinfunction "1_3") (pintype "passive"))
    )
    (net (code "80") (name "Net-(R3C-1)") (class "Default")
      (node (ref "ADD1") (pin "2") (pinfunction "2_2") (pintype "passive"))
      (node (ref "R3") (pin "5") (pinfunction "1_5") (pintype "passive"))
    )
    (net (code "81") (name "Net-(R3D-1)") (class "Default")
      (node (ref "ADD0") (pin "2") (pinfunction "2_2") (pintype "passive"))
      (node (ref "R3") (pin "7") (pinfunction "1_7") (pintype "passive"))
    )
    (net (code "82") (name "Net-(R8B-1)") (class "Default")
      (node (ref "D1") (pin "2") (pinfunction "2_2") (pintype "bidirectional"))
      (node (ref "R8") (pin "3") (pinfunction "1_3") (pintype "passive"))
    )
    (net (code "83") (name "Net-(R8C-1)") (class "Default")
      (node (ref "D1") (pin "3") (pinfunction "3_3") (pintype "bidirectional"))
      (node (ref "R8") (pin "5") (pinfunction "1_5") (pintype "passive"))
    )
    (net (code "84") (name "Net-(R8D-1)") (class "Default")
      (node (ref "D1") (pin "4") (pinfunction "4_4") (pintype "bidirectional"))
      (node (ref "R8") (pin "7") (pinfunction "1_7") (pintype "passive"))
    )
    (net (code "85") (name "Net-(R9B-1)") (class "Default")
      (node (ref "D1") (pin "6") (pinfunction "6_6") (pintype "bidirectional"))
      (node (ref "R9") (pin "3") (pinfunction "1_3") (pintype "passive"))
    )
    (net (code "86") (name "Net-(R9C-1)") (class "Default")
      (node (ref "D1") (pin "7") (pinfunction "7_7") (pintype "bidirectional"))
      (node (ref "R9") (pin "5") (pinfunction "1_5") (pintype "passive"))
    )
    (net (code "87") (name "Net-(R9D-1)") (class "Default")
      (node (ref "D1") (pin "8") (pinfunction "8_8") (pintype "bidirectional"))
      (node (ref "R9") (pin "7") (pinfunction "1_7") (pintype "passive"))
    )
    (net (code "88") (name "RESET") (class "Default")
      (node (ref "ICSP") (pin "5") (pinfunction "5_5") (pintype "passive"))
      (node (ref "U1") (pin "4") (pinfunction "PB3(PCINT11/ADC9/~{RESET}/DW)_4") (pintype "bidirectional"))
    )
    (net (code "89") (name "SCK") (class "Default")
      (node (ref "IC1") (pin "11") (pinfunction "SCK_11") (pintype "input"))
      (node (ref "IC2") (pin "11") (pinfunction "SCK_11") (pintype "input"))
      (node (ref "IC3") (pin "11") (pinfunction "SCK_11") (pintype "input"))
      (node (ref "IC4") (pin "11") (pinfunction "SCK_11") (pintype "input"))
      (node (ref "U1") (pin "10") (pinfunction "PA3(PCINT3/ADC3/AIN10/TOCC2/T0/XCK0/SCK)_10") (pintype "bidirectional"))
    )
    (net (code "90") (name "SCL{slash}SCLK") (class "Default")
      (node (ref "I2C") (pin "7") (pinfunction "7_7") (pintype "passive"))
      (node (ref "ICSP") (pin "3") (pinfunction "3_3") (pintype "passive"))
      (node (ref "NEO") (pin "2") (pinfunction "2_2") (pintype "passive"))
      (node (ref "R11") (pin "2") (pinfunction "2_2") (pintype "passive"))
      (node (ref "U1") (pin "9") (pinfunction "PA4(PCINT4/ADC4/AIN11/TOCC3/T1/RXD1/SCL/SCK)_9") (pintype "bidirectional"))
    )
    (net (code "91") (name "SDA{slash}MOSI") (class "Default")
      (node (ref "I2C") (pin "5") (pinfunction "5_5") (pintype "passive"))
      (node (ref "ICSP") (pin "4") (pinfunction "4_4") (pintype "passive"))
      (node (ref "R10") (pin "2") (pinfunction "2_2") (pintype "passive"))
      (node (ref "U1") (pin "7") (pinfunction "PA6(PCINT6/ADC6/ACO1/TOCC5/XCK1/SDA/MOSI)_7") (pintype "bidirectional"))
    )
    (net (code "92") (name "SER") (class "Default")
      (node (ref "IC1") (pin "14") (pinfunction "SER_14") (pintype "input"))
      (node (ref "U1") (pin "12") (pinfunction "PA1(PCINT1/ADC1/AIN00/TOCC0/TXD0/MOSI)_12") (pintype "bidirectional"))
    )
    (net (code "93") (name "XLAT") (class "Default")
      (node (ref "IC1") (pin "12") (pinfunction "RCK_12") (pintype "input"))
      (node (ref "IC2") (pin "12") (pinfunction "RCK_12") (pintype "input"))
      (node (ref "IC3") (pin "12") (pinfunction "RCK_12") (pintype "input"))
      (node (ref "IC4") (pin "12") (pinfunction "RCK_12") (pintype "input"))
      (node (ref "U1") (pin "3") (pinfunction "PB1(PCINT9/ADC10/XTAL2/INT0)_3") (pintype "bidirectional"))
    )
    (net (code "94") (name "unconnected-(I2C-Pad9)") (class "Default")
      (node (ref "I2C") (pin "9") (pinfunction "9_9") (pintype "passive"))
    )
    (net (code "95") (name "unconnected-(I2C-Pad10)") (class "Default")
      (node (ref "I2C") (pin "10") (pinfunction "10_10") (pintype "passive"))
    )
    (net (code "96") (name "unconnected-(IC4A-QH*-Pad9)") (class "Default")
      (node (ref "IC4") (pin "9") (pinfunction "QH*_9") (pintype "tri_state"))
    )
  )
)
